# SCH_New-Project_2025-02-11.net
KiCad netlist of a schematic drawn in EasyEDA
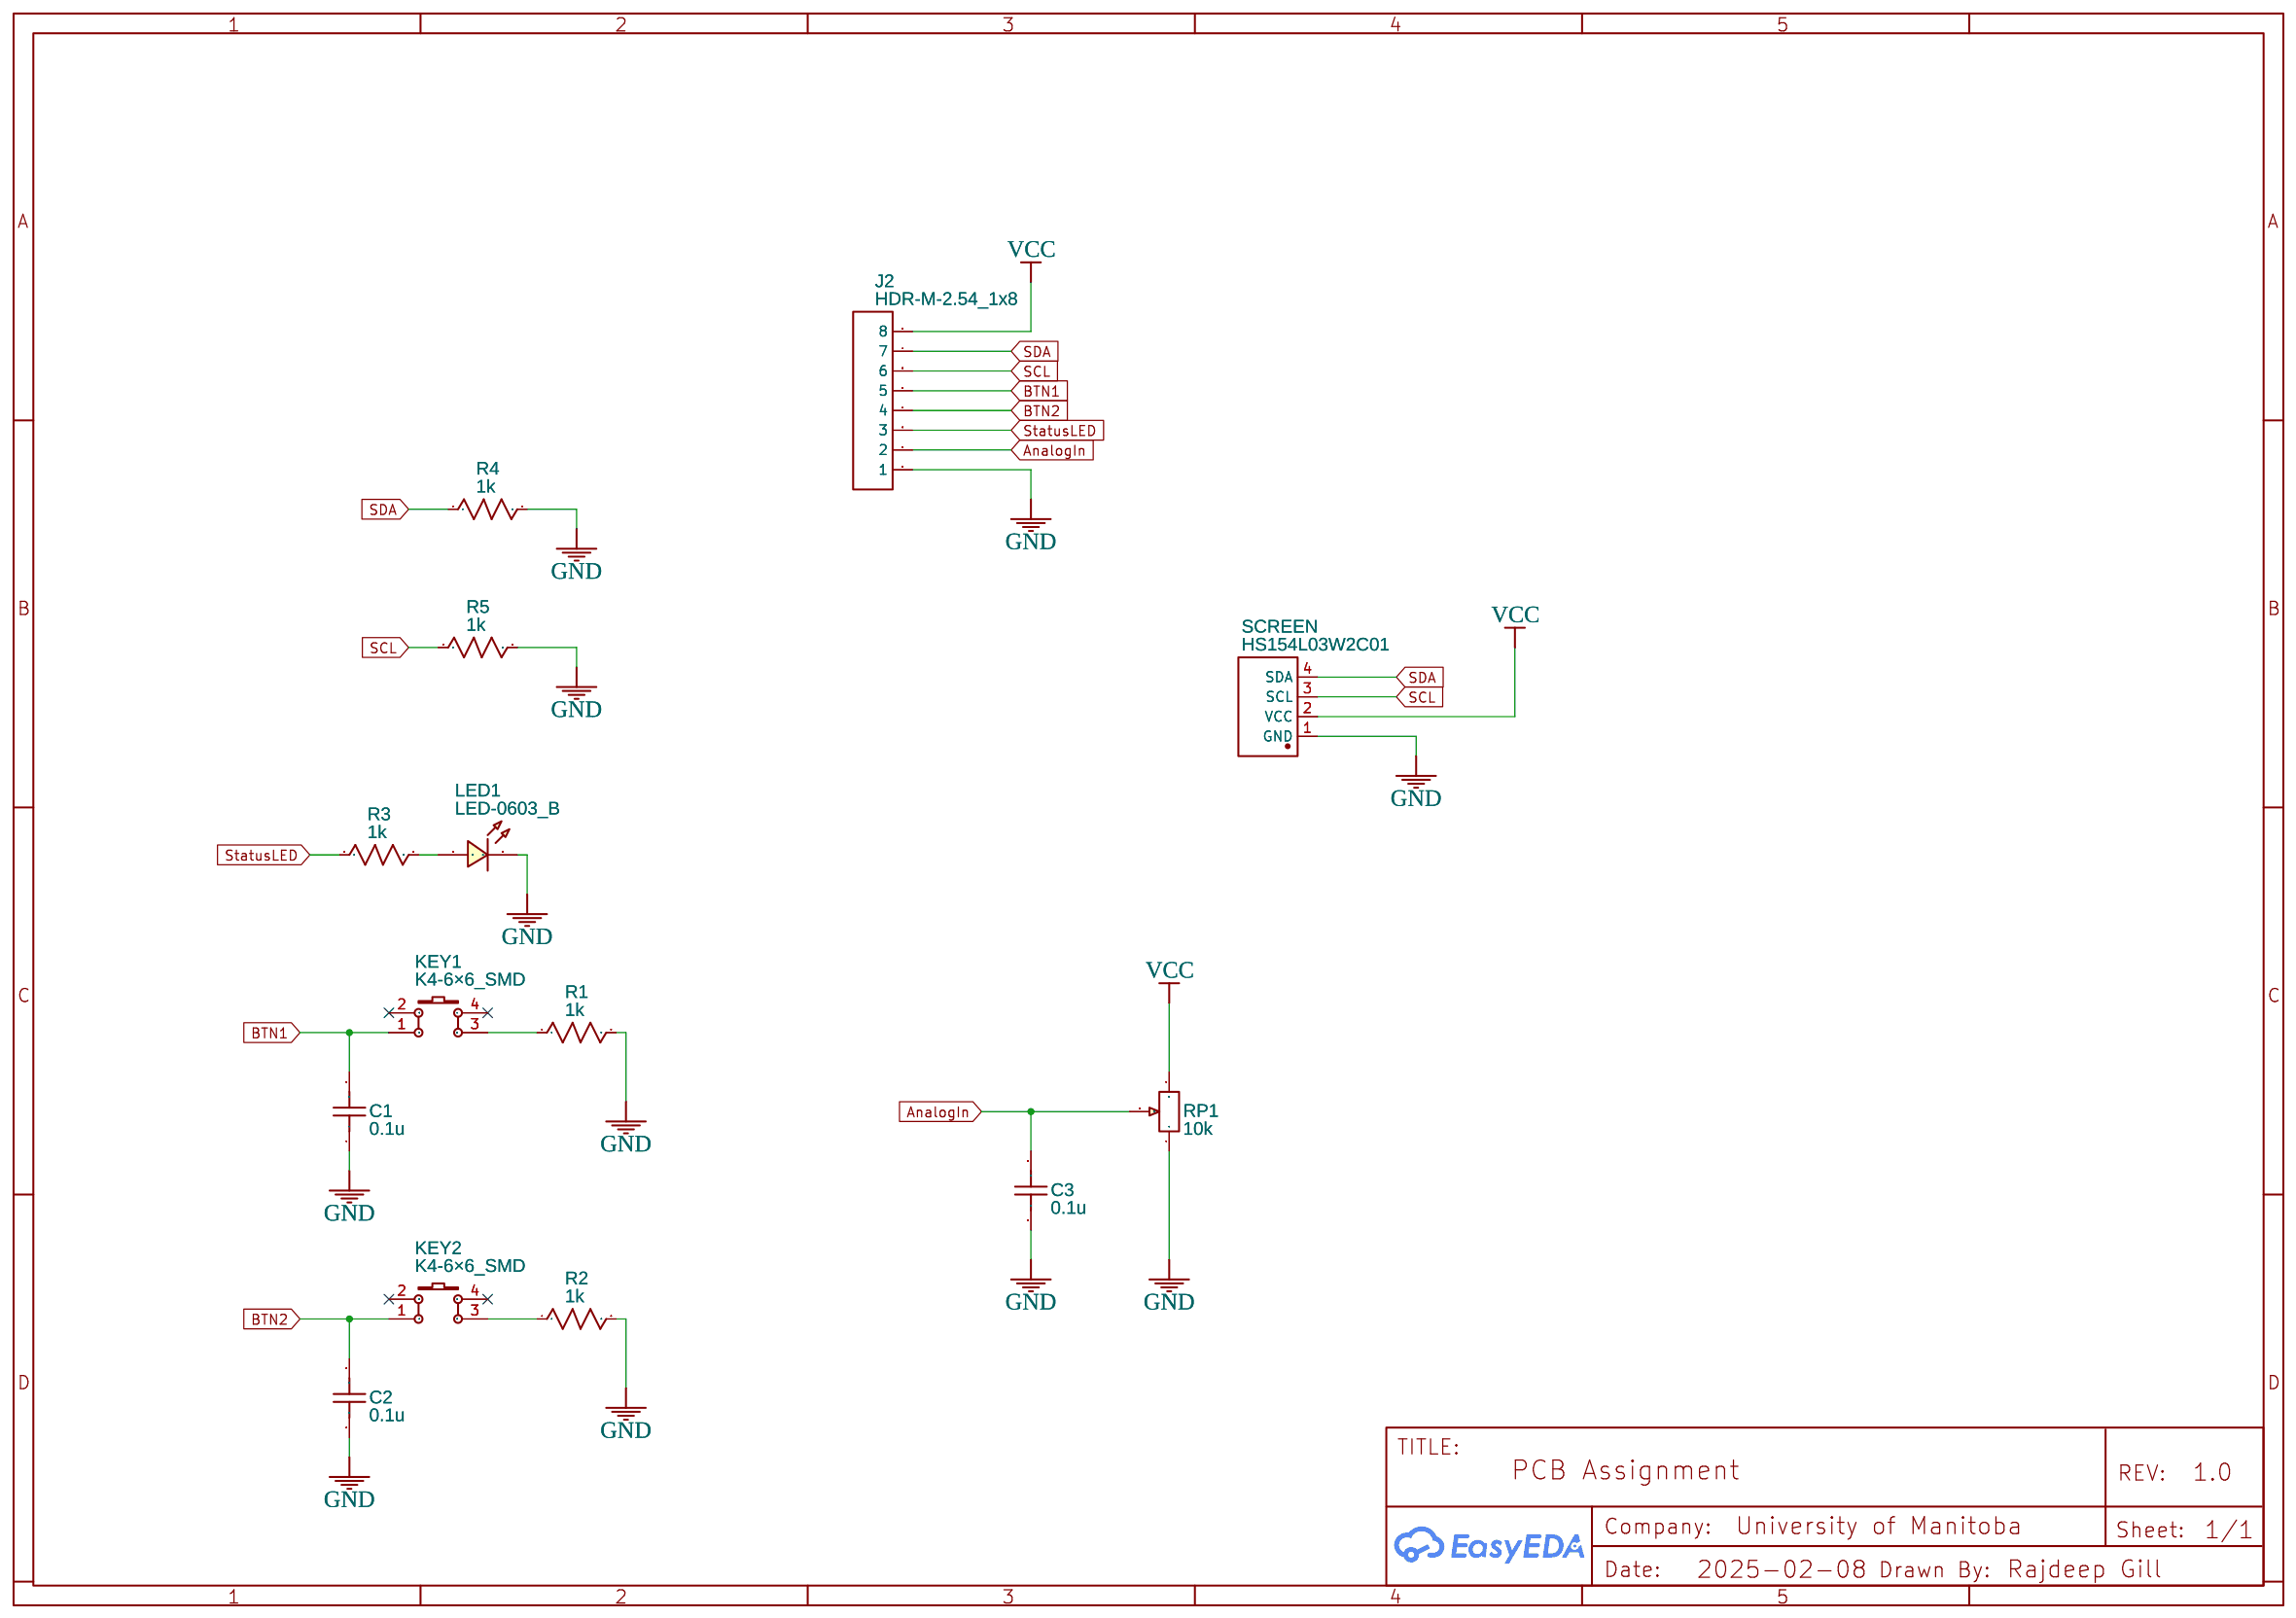
[diagram p0: schematic sheet]

(export (version "E")
  (design (tool "Eeschema 10.0.6"))
  (components
    (comp (ref "C1") (value "0.1u") (libsource (lib "") (part "C_0603_US")))
    (comp (ref "C2") (value "0.1u") (libsource (lib "") (part "C_0603_US")))
    (comp (ref "C3") (value "0.1u") (libsource (lib "") (part "C_0603_US")))
    (comp (ref "J2") (value "HDR-M-2.54_1x8") (libsource (lib "") (part "HDR-M-2.54_1x8")))
    (comp (ref "KEY1")
      (value "K4-6×6_SMD")
      (fields (field (name "Manufacturer Part") "K2-6639SP-D4SC-04") (field (name "Manufacturer") "韩国韩荣"))
      (libsource (lib "") (part "K4-6×6_SMD"))
    )
    (comp (ref "KEY2")
      (value "K4-6×6_SMD")
      (fields (field (name "Manufacturer Part") "K2-6639SP-D4SC-04") (field (name "Manufacturer") "韩国韩荣"))
      (libsource (lib "") (part "K4-6×6_SMD"))
    )
    (comp (ref "LED1")
      (value "LED-0603_B")
      (fields
        (field (name "Manufacturer Part") "19-217/BHC-ZL1M2RY/3T")
        (field (name "Manufacturer") "EVERLIGHT(台湾亿光)")
      )
      (libsource (lib "") (part "LED-0603_B"))
    )
    (comp (ref "R1") (value "1k") (libsource (lib "") (part "R_0603_US")))
    (comp (ref "R2") (value "1k") (libsource (lib "") (part "R_0603_US")))
    (comp (ref "R3") (value "1k") (libsource (lib "") (part "R_0603_US")))
    (comp (ref "R4") (value "1k") (libsource (lib "") (part "R_0603_US")))
    (comp (ref "R5") (value "1k") (libsource (lib "") (part "R_0603_US")))
    (comp (ref "RP1") (value "10k") (libsource (lib "") (part "R_3386P_EU")))
    (comp (ref "SCREEN")
      (value "HS154L03W2C01")
      (fields (field (name "Manufacturer") "HS(汉昇)"))
      (libsource (lib "") (part "HS154L03W2C01"))
    )
  )
  (nets
    (net (code "1") (name "AnalogIn") (class "Default")
      (node (ref "C3") (pin "2") (pinfunction "2_2") (pintype "unspecified"))
      (node (ref "J2") (pin "2") (pinfunction "2_2") (pintype "unspecified"))
      (node (ref "RP1") (pin "2") (pinfunction "2_2") (pintype "input"))
    )
    (net (code "2") (name "BTN1") (class "Default")
      (node (ref "C1") (pin "2") (pinfunction "2_2") (pintype "unspecified"))
      (node (ref "J2") (pin "5") (pinfunction "5_5") (pintype "unspecified"))
      (node (ref "KEY1") (pin "1") (pinfunction "1_1") (pintype "unspecified"))
    )
    (net (code "3") (name "BTN2") (class "Default")
      (node (ref "C2") (pin "2") (pinfunction "2_2") (pintype "unspecified"))
      (node (ref "J2") (pin "4") (pinfunction "4_4") (pintype "unspecified"))
      (node (ref "KEY2") (pin "1") (pinfunction "1_1") (pintype "unspecified"))
    )
    (net (code "4") (name "GND") (class "Default")
      (node (ref "C1") (pin "1") (pinfunction "1_1") (pintype "unspecified"))
      (node (ref "C2") (pin "1") (pinfunction "1_1") (pintype "unspecified"))
      (node (ref "C3") (pin "1") (pinfunction "1_1") (pintype "unspecified"))
      (node (ref "J2") (pin "1") (pinfunction "1_1") (pintype "unspecified"))
      (node (ref "LED1") (pin "2") (pinfunction "2_2") (pintype "unspecified"))
      (node (ref "R1") (pin "2") (pinfunction "2_2") (pintype "unspecified"))
      (node (ref "R2") (pin "2") (pinfunction "2_2") (pintype "unspecified"))
      (node (ref "R4") (pin "2") (pinfunction "2_2") (pintype "unspecified"))
      (node (ref "R5") (pin "2") (pinfunction "2_2") (pintype "unspecified"))
      (node (ref "RP1") (pin "1") (pinfunction "1_1") (pintype "input"))
      (node (ref "SCREEN") (pin "1") (pinfunction "GND_1") (pintype "unspecified"))
    )
    (net (code "5") (name "Net-(KEY1-Pad3)") (class "Default")
      (node (ref "KEY1") (pin "3") (pinfunction "3_3") (pintype "unspecified"))
      (node (ref "R1") (pin "1") (pinfunction "1_1") (pintype "unspecified"))
    )
    (net (code "6") (name "Net-(KEY2-Pad3)") (class "Default")
      (node (ref "KEY2") (pin "3") (pinfunction "3_3") (pintype "unspecified"))
      (node (ref "R2") (pin "1") (pinfunction "1_1") (pintype "unspecified"))
    )
    (net (code "7") (name "Net-(LED1-Pad1)") (class "Default")
      (node (ref "LED1") (pin "1") (pinfunction "1_1") (pintype "unspecified"))
      (node (ref "R3") (pin "2") (pinfunction "2_2") (pintype "unspecified"))
    )
    (net (code "8") (name "SCL") (class "Default")
      (node (ref "J2") (pin "6") (pinfunction "6_6") (pintype "unspecified"))
      (node (ref "R5") (pin "1") (pinfunction "1_1") (pintype "unspecified"))
      (node (ref "SCREEN") (pin "3") (pinfunction "SCL_3") (pintype "unspecified"))
    )
    (net (code "9") (name "SDA") (class "Default")
      (node (ref "J2") (pin "7") (pinfunction "7_7") (pintype "unspecified"))
      (node (ref "R4") (pin "1") (pinfunction "1_1") (pintype "unspecified"))
      (node (ref "SCREEN") (pin "4") (pinfunction "SDA_4") (pintype "unspecified"))
    )
    (net (code "10") (name "StatusLED") (class "Default")
      (node (ref "J2") (pin "3") (pinfunction "3_3") (pintype "unspecified"))
      (node (ref "R3") (pin "1") (pinfunction "1_1") (pintype "unspecified"))
    )
    (net (code "11") (name "VCC") (class "Default")
      (node (ref "J2") (pin "8") (pinfunction "8_8") (pintype "unspecified"))
      (node (ref "RP1") (pin "3") (pinfunction "3_3") (pintype "input"))
      (node (ref "SCREEN") (pin "2") (pinfunction "VCC_2") (pintype "unspecified"))
    )
    (net (code "12") (name "unconnected-(KEY1-Pad2)") (class "Default")
      (node (ref "KEY1") (pin "2") (pinfunction "2_2") (pintype "unspecified+no_connect"))
    )
    (net (code "13") (name "unconnected-(KEY1-Pad4)") (class "Default")
      (node (ref "KEY1") (pin "4") (pinfunction "4_4") (pintype "unspecified+no_connect"))
    )
    (net (code "14") (name "unconnected-(KEY2-Pad2)") (class "Default")
      (node (ref "KEY2") (pin "2") (pinfunction "2_2") (pintype "unspecified+no_connect"))
    )
    (net (code "15") (name "unconnected-(KEY2-Pad4)") (class "Default")
      (node (ref "KEY2") (pin "4") (pinfunction "4_4") (pintype "unspecified+no_connect"))
    )
  )
)
